# BSB-LAN.net
KiCad netlist of a schematic drawn in EAGLE
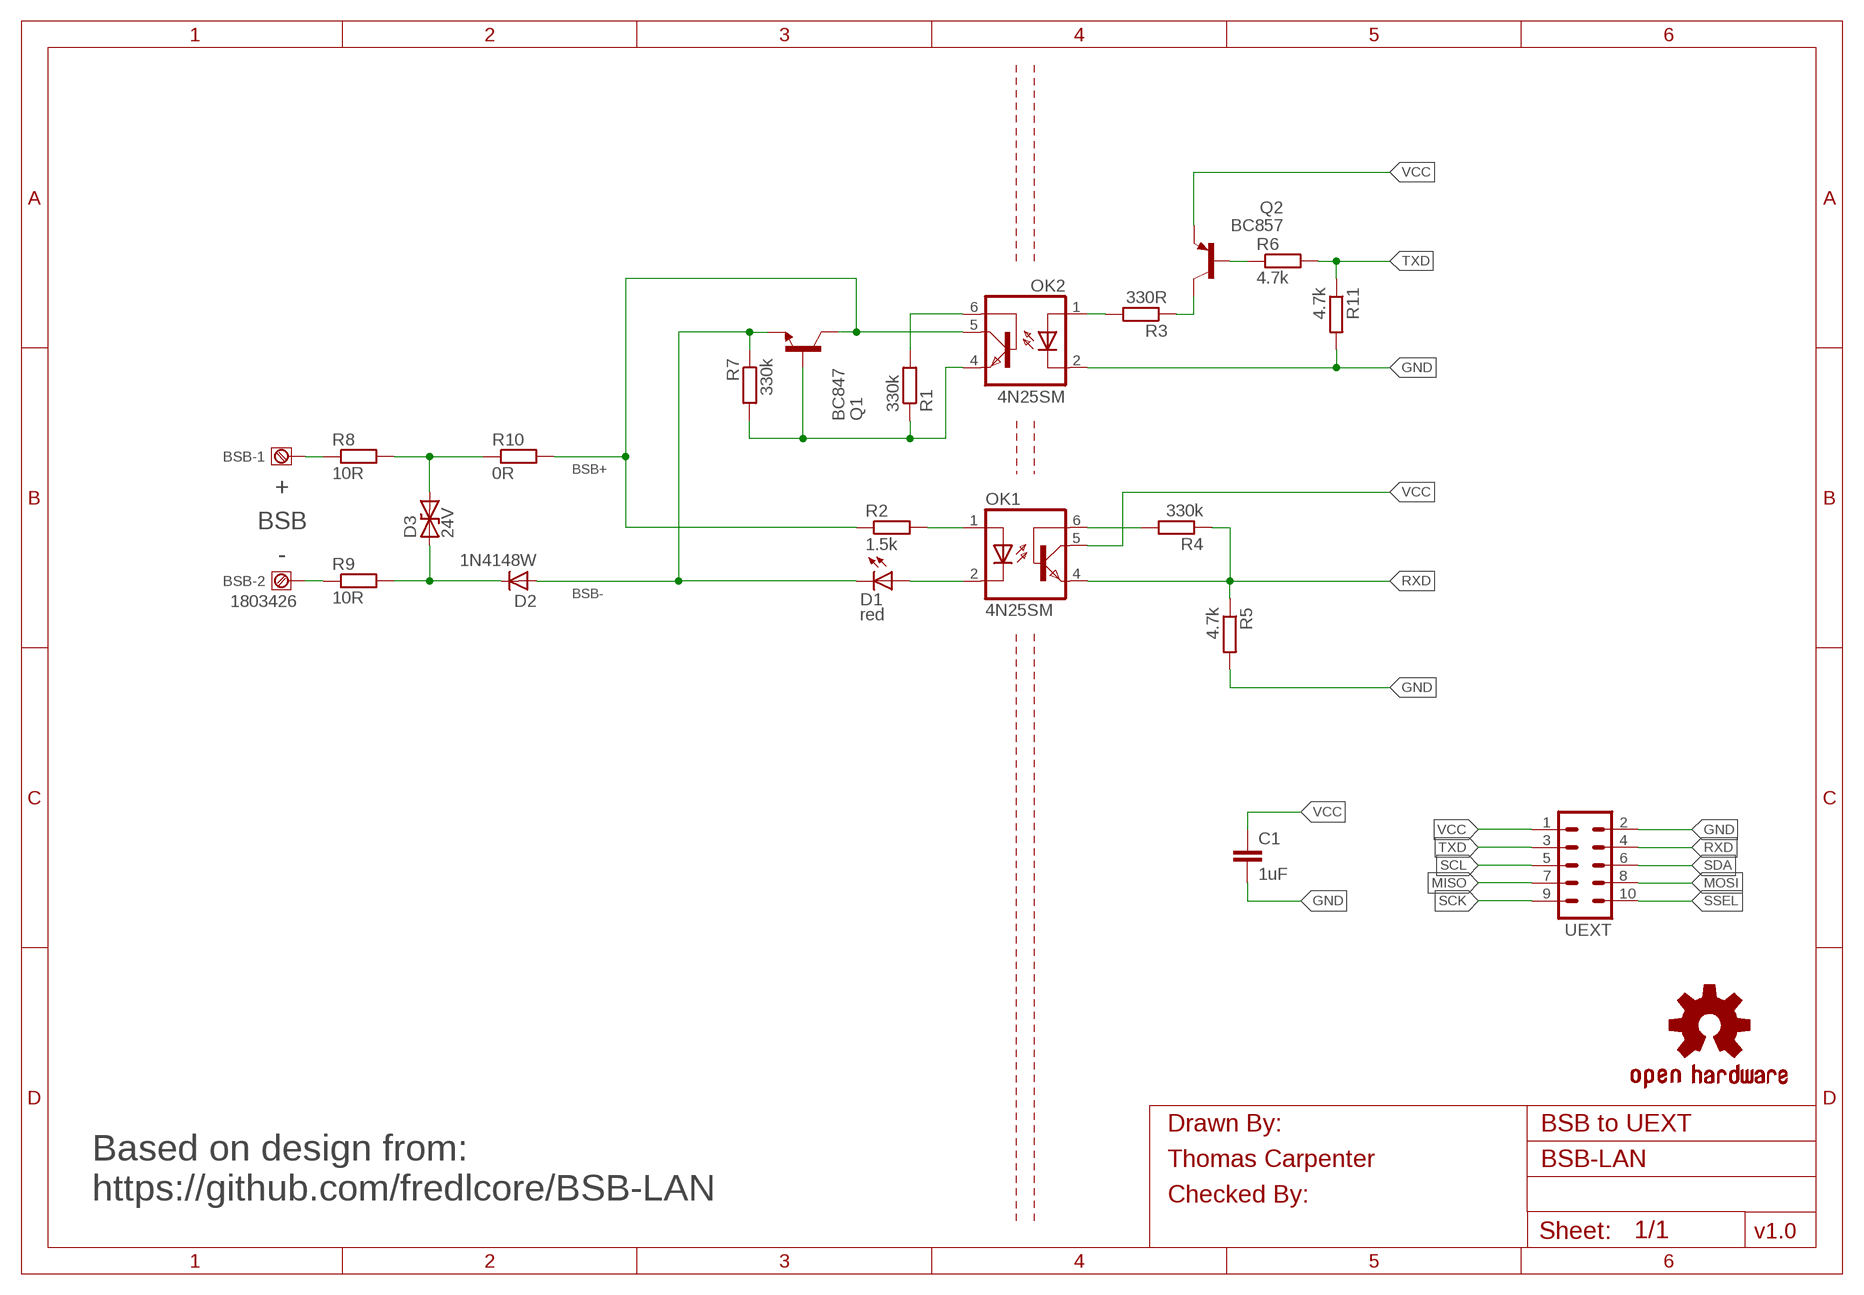
[diagram p0: schematic, sheet 1]

(export (version "E")
  (design (tool "Eeschema 10.0.6"))
  (components
    (comp (ref "BSB")
      (value "1803426")
      (footprint "eagle-import:1803426")
      (fields (field (name "LCSC_PART") "C480514") (field (name "LCSC_PART_1") "C480514"))
      (libsource (lib "eagle-import") (part "1803426"))
    )
    (comp (ref "C1")
      (value "1uF")
      (footprint "eagle-import:C0805")
      (fields (field (name "LCSC_PART") "C28323"))
      (libsource (lib "eagle-import") (part "C-EUC0805"))
    )
    (comp (ref "D1")
      (value "red")
      (footprint "eagle-import:CHIPLED_0805")
      (fields (field (name "LCSC_PART") "C84256"))
      (libsource (lib "eagle-import") (part "LEDCHIPLED_0805"))
    )
    (comp (ref "D2")
      (value "1N4148W")
      (footprint "eagle-import:SOD123")
      (fields (field (name "LCSC_PART") "C81598"))
      (libsource (lib "eagle-import") (part "DIODE-SOD123"))
    )
    (comp (ref "D3")
      (value "24V")
      (footprint "eagle-import:SMBG")
      (fields (field (name "LCSC_PART") "C83268"))
      (libsource (lib "eagle-import") (part "TVS-BIDIRSMB"))
    )
    (comp (ref "OK1")
      (value "4N25SM")
      (footprint "eagle-import:DIL6-SMD")
      (fields (field (name "LCSC_PART") "C258246") (field (name "LCSC_PART_1") "C258246"))
      (libsource (lib "eagle-import") (part "4N?MS25"))
    )
    (comp (ref "OK2")
      (value "4N25SM")
      (footprint "eagle-import:DIL6-SMD")
      (fields (field (name "LCSC_PART") "C258246") (field (name "LCSC_PART_1") "C258246"))
      (libsource (lib "eagle-import") (part "4N?MS25"))
    )
    (comp (ref "Q1")
      (value "BC847")
      (footprint "eagle-import:SOT23")
      (fields (field (name "LCSC_PART") "C130417") (field (name "LCSC_PART_1") "C130417"))
      (libsource (lib "eagle-import") (part "BC847"))
    )
    (comp (ref "Q2")
      (value "BC857")
      (footprint "eagle-import:SOT23-BEC")
      (fields (field (name "LCSC_PART") "C426782") (field (name "LCSC_PART_1") "C426782"))
      (libsource (lib "eagle-import") (part "BC857"))
    )
    (comp (ref "R1")
      (value "330k")
      (footprint "eagle-import:R0805")
      (fields (field (name "LCSC_PART") "C17629"))
      (libsource (lib "eagle-import") (part "R-EU_R0805"))
    )
    (comp (ref "R2")
      (value "1.5k")
      (footprint "eagle-import:R0805")
      (fields (field (name "LCSC_PART") "C4310"))
      (libsource (lib "eagle-import") (part "R-EU_R0805"))
    )
    (comp (ref "R3")
      (value "330R")
      (footprint "eagle-import:R0805")
      (fields (field (name "LCSC_PART") "C17630"))
      (libsource (lib "eagle-import") (part "R-EU_R0805"))
    )
    (comp (ref "R4")
      (value "330k")
      (footprint "eagle-import:R0805")
      (fields (field (name "LCSC_PART") "C17629"))
      (libsource (lib "eagle-import") (part "R-EU_R0805"))
    )
    (comp (ref "R5")
      (value "4.7k")
      (footprint "eagle-import:R0805")
      (fields (field (name "LCSC_PART") "C17673"))
      (libsource (lib "eagle-import") (part "R-EU_R0805"))
    )
    (comp (ref "R6")
      (value "4.7k")
      (footprint "eagle-import:R0805")
      (fields (field (name "LCSC_PART") "C17673"))
      (libsource (lib "eagle-import") (part "R-EU_R0805"))
    )
    (comp (ref "R7")
      (value "330k")
      (footprint "eagle-import:R0805")
      (fields (field (name "LCSC_PART") "C17629"))
      (libsource (lib "eagle-import") (part "R-EU_R0805"))
    )
    (comp (ref "R8")
      (value "10R")
      (footprint "eagle-import:R1206")
      (fields (field (name "LCSC_PART") "C17903"))
      (libsource (lib "eagle-import") (part "R-EU_R1206"))
    )
    (comp (ref "R9")
      (value "10R")
      (footprint "eagle-import:R1206")
      (fields (field (name "LCSC_PART") "C17903"))
      (libsource (lib "eagle-import") (part "R-EU_R1206"))
    )
    (comp (ref "R10")
      (value "0R")
      (footprint "eagle-import:R1206L")
      (fields (field (name "LCSC_PART") "C17888"))
      (libsource (lib "eagle-import") (part "R-EU_R1206L"))
    )
    (comp (ref "R11")
      (value "4.7k")
      (footprint "eagle-import:R0805L")
      (fields (field (name "LCSC_PART") "C17673"))
      (libsource (lib "eagle-import") (part "R-EU_R0805L"))
    )
    (comp (ref "U$3")
      (value "DNI")
      (footprint "eagle-import:OSHW-LOGO-M")
      (libsource (lib "eagle-import") (part "OSHW-LOGOM"))
    )
    (comp (ref "UEXT")
      (value "ML10F")
      (footprint "eagle-import:ML10F")
      (libsource (lib "eagle-import") (part "ML10F"))
    )
  )
  (nets
    (net (code "1") (name "/BSB+") (class "Default")
      (node (ref "OK2") (pin "5") (pinfunction "COL_5") (pintype "passive"))
      (node (ref "Q1") (pin "3") (pinfunction "C_3") (pintype "passive"))
      (node (ref "R10") (pin "2") (pinfunction "2_2") (pintype "passive"))
      (node (ref "R2") (pin "1") (pinfunction "1_1") (pintype "passive"))
    )
    (net (code "2") (name "/BSB-") (class "Default")
      (node (ref "D1") (pin "C") (pinfunction "C_C") (pintype "passive"))
      (node (ref "D2") (pin "A") (pinfunction "A_A") (pintype "passive"))
      (node (ref "Q1") (pin "2") (pinfunction "E_2") (pintype "passive"))
      (node (ref "R7") (pin "1") (pinfunction "1_1") (pintype "passive"))
    )
    (net (code "3") (name "GND") (class "Default")
      (node (ref "C1") (pin "2") (pinfunction "2_2") (pintype "passive"))
      (node (ref "OK2") (pin "2") (pinfunction "C_2") (pintype "passive"))
      (node (ref "R11") (pin "2") (pinfunction "2_2") (pintype "passive"))
      (node (ref "R5") (pin "2") (pinfunction "2_2") (pintype "passive"))
      (node (ref "UEXT") (pin "2") (pinfunction "2_2") (pintype "passive"))
    )
    (net (code "4") (name "MISO") (class "Default")
      (node (ref "UEXT") (pin "7") (pinfunction "7_7") (pintype "passive"))
    )
    (net (code "5") (name "MOSI") (class "Default")
      (node (ref "UEXT") (pin "8") (pinfunction "8_8") (pintype "passive"))
    )
    (net (code "6") (name "Net-(BSB-Pad1)") (class "Default")
      (node (ref "BSB") (pin "1") (pinfunction "1_1") (pintype "passive"))
      (node (ref "R8") (pin "1") (pinfunction "1_1") (pintype "passive"))
    )
    (net (code "7") (name "Net-(BSBB-1)") (class "Default")
      (node (ref "BSB") (pin "2") (pinfunction "1_2") (pintype "passive"))
      (node (ref "R9") (pin "1") (pinfunction "1_1") (pintype "passive"))
    )
    (net (code "8") (name "Net-(D2-PadC)") (class "Default")
      (node (ref "D2") (pin "C") (pinfunction "C_C") (pintype "passive"))
      (node (ref "D3") (pin "1") (pinfunction "1_1") (pintype "passive"))
      (node (ref "R9") (pin "2") (pinfunction "2_2") (pintype "passive"))
    )
    (net (code "9") (name "Net-(D3-Pad2)") (class "Default")
      (node (ref "D3") (pin "2") (pinfunction "2_2") (pintype "passive"))
      (node (ref "R10") (pin "1") (pinfunction "1_1") (pintype "passive"))
      (node (ref "R8") (pin "2") (pinfunction "2_2") (pintype "passive"))
    )
    (net (code "10") (name "Net-(OK1-A)") (class "Default")
      (node (ref "OK1") (pin "1") (pinfunction "A_1") (pintype "passive"))
      (node (ref "R2") (pin "2") (pinfunction "2_2") (pintype "passive"))
    )
    (net (code "11") (name "Net-(OK1-BAS)") (class "Default")
      (node (ref "OK1") (pin "6") (pinfunction "BAS_6") (pintype "passive"))
      (node (ref "R4") (pin "2") (pinfunction "2_2") (pintype "passive"))
    )
    (net (code "12") (name "Net-(OK1-C)") (class "Default")
      (node (ref "D1") (pin "A") (pinfunction "A_A") (pintype "passive"))
      (node (ref "OK1") (pin "2") (pinfunction "C_2") (pintype "passive"))
    )
    (net (code "13") (name "Net-(OK2-A)") (class "Default")
      (node (ref "OK2") (pin "1") (pinfunction "A_1") (pintype "passive"))
      (node (ref "R3") (pin "2") (pinfunction "2_2") (pintype "passive"))
    )
    (net (code "14") (name "Net-(OK2-BAS)") (class "Default")
      (node (ref "OK2") (pin "6") (pinfunction "BAS_6") (pintype "passive"))
      (node (ref "R1") (pin "2") (pinfunction "2_2") (pintype "passive"))
    )
    (net (code "15") (name "Net-(OK2-EMI)") (class "Default")
      (node (ref "OK2") (pin "4") (pinfunction "EMI_4") (pintype "passive"))
      (node (ref "Q1") (pin "1") (pinfunction "B_1") (pintype "passive"))
      (node (ref "R1") (pin "1") (pinfunction "1_1") (pintype "passive"))
      (node (ref "R7") (pin "2") (pinfunction "2_2") (pintype "passive"))
    )
    (net (code "16") (name "Net-(Q2-PadB)") (class "Default")
      (node (ref "Q2") (pin "B") (pinfunction "B_B") (pintype "passive"))
      (node (ref "R6") (pin "1") (pinfunction "1_1") (pintype "passive"))
    )
    (net (code "17") (name "Net-(Q2-PadC)") (class "Default")
      (node (ref "Q2") (pin "C") (pinfunction "C_C") (pintype "passive"))
      (node (ref "R3") (pin "1") (pinfunction "1_1") (pintype "passive"))
    )
    (net (code "18") (name "RXD") (class "Default")
      (node (ref "OK1") (pin "4") (pinfunction "EMI_4") (pintype "passive"))
      (node (ref "R4") (pin "1") (pinfunction "1_1") (pintype "passive"))
      (node (ref "R5") (pin "1") (pinfunction "1_1") (pintype "passive"))
      (node (ref "UEXT") (pin "4") (pinfunction "4_4") (pintype "passive"))
    )
    (net (code "19") (name "SCK") (class "Default")
      (node (ref "UEXT") (pin "9") (pinfunction "9_9") (pintype "passive"))
    )
    (net (code "20") (name "SCL") (class "Default")
      (node (ref "UEXT") (pin "5") (pinfunction "5_5") (pintype "passive"))
    )
    (net (code "21") (name "SDA") (class "Default")
      (node (ref "UEXT") (pin "6") (pinfunction "6_6") (pintype "passive"))
    )
    (net (code "22") (name "SSEL") (class "Default")
      (node (ref "UEXT") (pin "10") (pinfunction "10_10") (pintype "passive"))
    )
    (net (code "23") (name "TXD") (class "Default")
      (node (ref "R11") (pin "1") (pinfunction "1_1") (pintype "passive"))
      (node (ref "R6") (pin "2") (pinfunction "2_2") (pintype "passive"))
      (node (ref "UEXT") (pin "3") (pinfunction "3_3") (pintype "passive"))
    )
    (net (code "24") (name "VCC") (class "Default")
      (node (ref "C1") (pin "1") (pinfunction "1_1") (pintype "passive"))
      (node (ref "OK1") (pin "5") (pinfunction "COL_5") (pintype "passive"))
      (node (ref "Q2") (pin "E") (pinfunction "E_E") (pintype "passive"))
      (node (ref "UEXT") (pin "1") (pinfunction "1_1") (pintype "passive"))
    )
  )
)
